# Digital_Ball_Sensor.net
KiCad netlist of a schematic drawn in Altium Designer
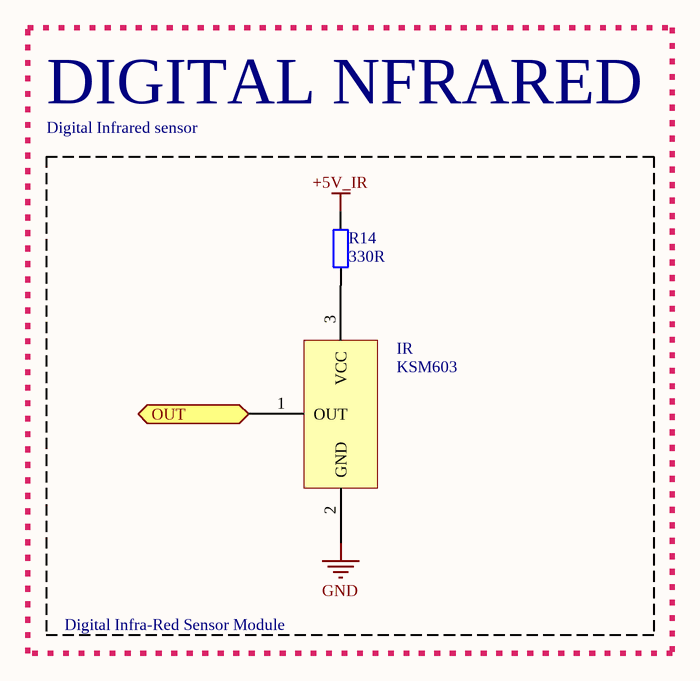
[diagram p0: Digital Ball Sensor.SchDoc]

(export (version "E")
  (design (tool "Eeschema 10.0.6"))
  (components
    (comp (ref "IR")
      (value "KSM603")
      (footprint "KSM603")
      (description "Generic Infra Red Sensor")
      (libsource (lib "CustomLibrary") (part "DIGITAL-IR-SENSOR"))
    )
    (comp (ref "R14") (value "330R") (footprint "RES1206") (libsource (lib "CustomLibrary") (part "RES")))
  )
  (nets
    (net (code "1") (name "+5V_IR") (class "Default")
      (node (ref "R14") (pin "2") (pinfunction "2_2") (pintype "passive"))
    )
    (net (code "2") (name "/OUT") (class "Default")
      (node (ref "IR") (pin "1") (pinfunction "OUT_1") (pintype "passive"))
    )
    (net (code "3") (name "GND") (class "Default")
      (node (ref "IR") (pin "2") (pinfunction "GND_2") (pintype "power_in"))
    )
    (net (code "4") (name "Net-(IR-VCC)") (class "Default")
      (node (ref "IR") (pin "3") (pinfunction "VCC_3") (pintype "power_in"))
      (node (ref "R14") (pin "1") (pinfunction "1_1") (pintype "passive"))
    )
  )
)
